# processor_board.net
KiCad netlist of a schematic drawn in EAGLE
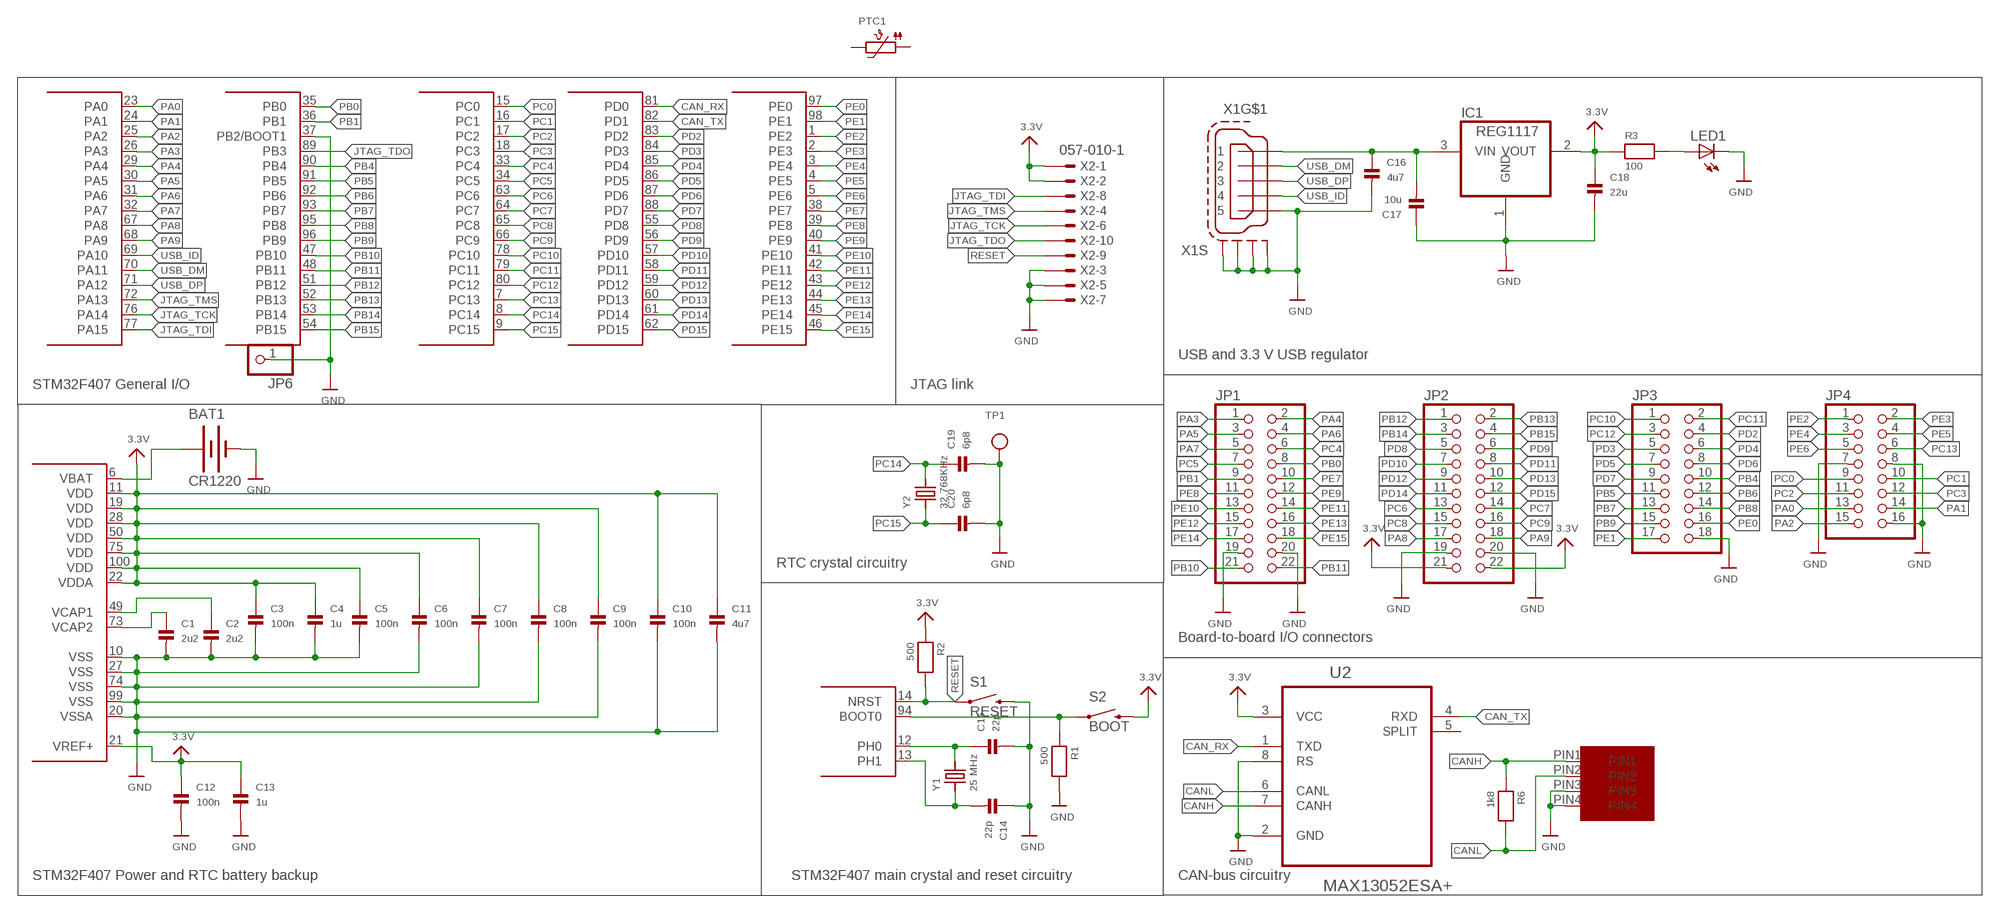
[diagram p0: schematic, sheet 1]

(export (version "E")
  (design (tool "Eeschema 10.0.6"))
  (components
    (comp (ref "BAT1")
      (value "CR1220")
      (footprint "eagle-import:BATTCON_12MM_PTH")
      (libsource (lib "eagle-import") (part "BATTERY12PTH"))
    )
    (comp (ref "C1")
      (value "2u2")
      (footprint "eagle-import:_0603MP")
      (libsource (lib "eagle-import") (part "CAP_CERAMIC_0603MP"))
    )
    (comp (ref "C2")
      (value "2u2")
      (footprint "eagle-import:_0603MP")
      (libsource (lib "eagle-import") (part "CAP_CERAMIC_0603MP"))
    )
    (comp (ref "C3")
      (value "100n")
      (footprint "eagle-import:_0603MP")
      (libsource (lib "eagle-import") (part "CAP_CERAMIC_0603MP"))
    )
    (comp (ref "C4")
      (value "1u")
      (footprint "eagle-import:_0603MP")
      (libsource (lib "eagle-import") (part "CAP_CERAMIC_0603MP"))
    )
    (comp (ref "C5")
      (value "100n")
      (footprint "eagle-import:_0603MP")
      (libsource (lib "eagle-import") (part "CAP_CERAMIC_0603MP"))
    )
    (comp (ref "C6")
      (value "100n")
      (footprint "eagle-import:_0603MP")
      (libsource (lib "eagle-import") (part "CAP_CERAMIC_0603MP"))
    )
    (comp (ref "C7")
      (value "100n")
      (footprint "eagle-import:_0603MP")
      (libsource (lib "eagle-import") (part "CAP_CERAMIC_0603MP"))
    )
    (comp (ref "C8")
      (value "100n")
      (footprint "eagle-import:_0603MP")
      (libsource (lib "eagle-import") (part "CAP_CERAMIC_0603MP"))
    )
    (comp (ref "C9")
      (value "100n")
      (footprint "eagle-import:_0603MP")
      (libsource (lib "eagle-import") (part "CAP_CERAMIC_0603MP"))
    )
    (comp (ref "C10")
      (value "100n")
      (footprint "eagle-import:_0603MP")
      (libsource (lib "eagle-import") (part "CAP_CERAMIC_0603MP"))
    )
    (comp (ref "C11")
      (value "4u7")
      (footprint "eagle-import:_0603MP")
      (libsource (lib "eagle-import") (part "CAP_CERAMIC_0603MP"))
    )
    (comp (ref "C12")
      (value "100n")
      (footprint "eagle-import:_0603MP")
      (libsource (lib "eagle-import") (part "CAP_CERAMIC_0603MP"))
    )
    (comp (ref "C13")
      (value "1u")
      (footprint "eagle-import:_0603MP")
      (libsource (lib "eagle-import") (part "CAP_CERAMIC_0603MP"))
    )
    (comp (ref "C14")
      (value "22p")
      (footprint "eagle-import:_0603MP")
      (libsource (lib "eagle-import") (part "CAP_CERAMIC_0603MP"))
    )
    (comp (ref "C15")
      (value "22p")
      (footprint "eagle-import:_0603MP")
      (libsource (lib "eagle-import") (part "CAP_CERAMIC_0603MP"))
    )
    (comp (ref "C16")
      (value "4u7")
      (footprint "eagle-import:_0603MP")
      (libsource (lib "eagle-import") (part "CAP_CERAMIC_0603MP"))
    )
    (comp (ref "C17")
      (value "10u")
      (footprint "eagle-import:_0603MP")
      (libsource (lib "eagle-import") (part "CAP_CERAMIC_0603MP"))
    )
    (comp (ref "C18")
      (value "22u")
      (footprint "eagle-import:_0603MP")
      (libsource (lib "eagle-import") (part "CAP_CERAMIC_0603MP"))
    )
    (comp (ref "C19")
      (value "6p8")
      (footprint "eagle-import:_0603MP")
      (libsource (lib "eagle-import") (part "CAP_CERAMIC_0603MP"))
    )
    (comp (ref "C20")
      (value "6p8")
      (footprint "eagle-import:_0603MP")
      (libsource (lib "eagle-import") (part "CAP_CERAMIC_0603MP"))
    )
    (comp (ref "IC1")
      (value "REG1117")
      (footprint "eagle-import:SOT223")
      (libsource (lib "eagle-import") (part "REG1117"))
    )
    (comp (ref "JP1")
      (value "PINHD-2X11")
      (footprint "eagle-import:2X11")
      (libsource (lib "eagle-import") (part "PINHD-2X11"))
    )
    (comp (ref "JP2")
      (value "PINHD-2X11")
      (footprint "eagle-import:2X11")
      (libsource (lib "eagle-import") (part "PINHD-2X11"))
    )
    (comp (ref "JP3")
      (value "PINHD-2X9")
      (footprint "eagle-import:2X09")
      (libsource (lib "eagle-import") (part "PINHD-2X9"))
    )
    (comp (ref "JP4")
      (value "PINHD-2X8")
      (footprint "eagle-import:2X08")
      (libsource (lib "eagle-import") (part "PINHD-2X8"))
    )
    (comp (ref "JP6")
      (value "PINHD-1X1")
      (footprint "eagle-import:1X01")
      (libsource (lib "eagle-import") (part "PINHD-1X1"))
    )
    (comp (ref "LED1")
      (value "LEDCHIPLED_1206")
      (footprint "eagle-import:CHIPLED_1206")
      (libsource (lib "eagle-import") (part "LEDCHIPLED_1206"))
    )
    (comp (ref "PTC1")
      (value "PTC1206")
      (footprint "eagle-import:1206")
      (libsource (lib "eagle-import") (part "PTC1206"))
    )
    (comp (ref "R1")
      (value "500")
      (footprint "eagle-import:_0603MP")
      (libsource (lib "eagle-import") (part "RESISTOR_0603MP"))
    )
    (comp (ref "R2")
      (value "500")
      (footprint "eagle-import:_0603MP")
      (libsource (lib "eagle-import") (part "RESISTOR_0603MP"))
    )
    (comp (ref "R3")
      (value "100")
      (footprint "eagle-import:_0603MP")
      (libsource (lib "eagle-import") (part "RESISTOR_0603MP"))
    )
    (comp (ref "R6")
      (value "1k8")
      (footprint "eagle-import:_0603MP")
      (libsource (lib "eagle-import") (part "RESISTOR_0603MP"))
    )
    (comp (ref "S1")
      (value "RESET")
      (footprint "eagle-import:TACTILE-SWITCH-1101NE")
      (libsource (lib "eagle-import") (part "SWITCH-MOMENTARY-2SMD-1101NE"))
    )
    (comp (ref "S2")
      (value "BOOT")
      (footprint "eagle-import:TACTILE-SWITCH-1101NE")
      (libsource (lib "eagle-import") (part "SWITCH-MOMENTARY-2SMD-1101NE"))
    )
    (comp (ref "TP1")
      (value "TESTPOINT0.1\"")
      (footprint "eagle-import:1X01_ROUND")
      (libsource (lib "eagle-import") (part "TESTPOINT0.1{dblquote}"))
    )
    (comp (ref "U$23")
      (value "MICROFIT4")
      (footprint "eagle-import:MICROFIT4SOCK")
      (libsource (lib "eagle-import") (part "MICROFIT4"))
    )
    (comp (ref "U1")
      (value "STM32F4-100")
      (footprint "eagle-import:SQFP-S-14X14-100")
      (libsource (lib "eagle-import") (part "STM32F4-100"))
    )
    (comp (ref "U2")
      (value "MAX13052ESA+")
      (footprint "eagle-import:SOIC127P600X175-8N")
      (libsource (lib "eagle-import") (part "MAX13052ESA+"))
    )
    (comp (ref "X1")
      (value "MINI-USB-SCHIELD-32005-201")
      (footprint "eagle-import:32005-201")
      (libsource (lib "eagle-import") (part "MINI-USB-SCHIELD-32005-201"))
    )
    (comp (ref "X2")
      (value "057-010-1")
      (footprint "eagle-import:057-010-1")
      (libsource (lib "eagle-import") (part "057-010-1"))
    )
    (comp (ref "Y1")
      (value "25 MHz")
      (footprint "eagle-import:CRYSTAL_2.5X2")
      (libsource (lib "eagle-import") (part "CRYSTAL2.5X2.0MM"))
    )
    (comp (ref "Y2")
      (value "32.768KHz")
      (footprint "eagle-import:CRYSTAL_CYL_2X6MM_SMT")
      (libsource (lib "eagle-import") (part "CRYSTAL32.768"))
    )
  )
  (nets
    (net (code "1") (name "3.3V") (class "Default")
      (node (ref "C10") (pin "1") (pinfunction "P$1_1") (pintype "passive"))
      (node (ref "C11") (pin "1") (pinfunction "P$1_1") (pintype "passive"))
      (node (ref "C12") (pin "1") (pinfunction "P$1_1") (pintype "passive"))
      (node (ref "C13") (pin "1") (pinfunction "P$1_1") (pintype "passive"))
      (node (ref "C18") (pin "1") (pinfunction "P$1_1") (pintype "passive"))
      (node (ref "C3") (pin "1") (pinfunction "P$1_1") (pintype "passive"))
      (node (ref "C4") (pin "1") (pinfunction "P$1_1") (pintype "passive"))
      (node (ref "C5") (pin "1") (pinfunction "P$1_1") (pintype "passive"))
      (node (ref "C6") (pin "1") (pinfunction "P$1_1") (pintype "passive"))
      (node (ref "C7") (pin "1") (pinfunction "P$1_1") (pintype "passive"))
      (node (ref "C8") (pin "1") (pinfunction "P$1_1") (pintype "passive"))
      (node (ref "C9") (pin "1") (pinfunction "P$1_1") (pintype "passive"))
      (node (ref "IC1") (pin "2") (pinfunction "VOUT_2") (pintype "output"))
      (node (ref "JP2") (pin "21") (pinfunction "21_21") (pintype "passive"))
      (node (ref "JP2") (pin "22") (pinfunction "22_22") (pintype "passive"))
      (node (ref "R2") (pin "1") (pinfunction "1_1") (pintype "passive"))
      (node (ref "R3") (pin "1") (pinfunction "1_1") (pintype "passive"))
      (node (ref "S2") (pin "2") (pinfunction "2_2") (pintype "passive"))
      (node (ref "U1") (pin "100") (pinfunction "VDD_100") (pintype "power_in"))
      (node (ref "U1") (pin "11") (pinfunction "VDD_11") (pintype "power_in"))
      (node (ref "U1") (pin "19") (pinfunction "VDD_19") (pintype "power_in"))
      (node (ref "U1") (pin "21") (pinfunction "VREF+_21") (pintype "passive"))
      (node (ref "U1") (pin "22") (pinfunction "VDDA_22") (pintype "power_in"))
      (node (ref "U1") (pin "28") (pinfunction "VDD_28") (pintype "power_in"))
      (node (ref "U1") (pin "50") (pinfunction "VDD_50") (pintype "power_in"))
      (node (ref "U1") (pin "75") (pinfunction "VDD_75") (pintype "power_in"))
      (node (ref "U2") (pin "3") (pinfunction "VCC_3") (pintype "power_in"))
      (node (ref "X2") (pin "1") (pinfunction "S_1") (pintype "passive"))
      (node (ref "X2") (pin "2") (pinfunction "S_2") (pintype "passive"))
    )
    (net (code "2") (name "CANH") (class "Default")
      (node (ref "R6") (pin "1") (pinfunction "1_1") (pintype "passive"))
      (node (ref "U$23") (pin "PIN1") (pinfunction "PIN1_PIN1") (pintype "bidirectional"))
      (node (ref "U2") (pin "7") (pinfunction "CANH_7") (pintype "input"))
    )
    (net (code "3") (name "CANL") (class "Default")
      (node (ref "R6") (pin "2") (pinfunction "2_2") (pintype "passive"))
      (node (ref "U$23") (pin "PIN2") (pinfunction "PIN2_PIN2") (pintype "bidirectional"))
      (node (ref "U2") (pin "6") (pinfunction "CANL_6") (pintype "input"))
    )
    (net (code "4") (name "CAN_RX") (class "Default")
      (node (ref "U1") (pin "81") (pinfunction "PD0_81") (pintype "bidirectional"))
      (node (ref "U2") (pin "1") (pinfunction "TXD_1") (pintype "input"))
    )
    (net (code "5") (name "CAN_TX") (class "Default")
      (node (ref "U1") (pin "82") (pinfunction "PD1_82") (pintype "bidirectional"))
      (node (ref "U2") (pin "4") (pinfunction "RXD_4") (pintype "output"))
    )
    (net (code "6") (name "GND") (class "Default")
      (node (ref "BAT1") (pin "GND") (pinfunction "-_GND") (pintype "power_in"))
      (node (ref "C1") (pin "2") (pinfunction "P$2_2") (pintype "passive"))
      (node (ref "C10") (pin "2") (pinfunction "P$2_2") (pintype "passive"))
      (node (ref "C11") (pin "2") (pinfunction "P$2_2") (pintype "passive"))
      (node (ref "C12") (pin "2") (pinfunction "P$2_2") (pintype "passive"))
      (node (ref "C13") (pin "2") (pinfunction "P$2_2") (pintype "passive"))
      (node (ref "C14") (pin "1") (pinfunction "P$1_1") (pintype "passive"))
      (node (ref "C15") (pin "2") (pinfunction "P$2_2") (pintype "passive"))
      (node (ref "C16") (pin "2") (pinfunction "P$2_2") (pintype "passive"))
      (node (ref "C17") (pin "1") (pinfunction "P$1_1") (pintype "passive"))
      (node (ref "C18") (pin "2") (pinfunction "P$2_2") (pintype "passive"))
      (node (ref "C19") (pin "2") (pinfunction "P$2_2") (pintype "passive"))
      (node (ref "C2") (pin "2") (pinfunction "P$2_2") (pintype "passive"))
      (node (ref "C20") (pin "2") (pinfunction "P$2_2") (pintype "passive"))
      (node (ref "C3") (pin "2") (pinfunction "P$2_2") (pintype "passive"))
      (node (ref "C4") (pin "2") (pinfunction "P$2_2") (pintype "passive"))
      (node (ref "C5") (pin "2") (pinfunction "P$2_2") (pintype "passive"))
      (node (ref "C6") (pin "2") (pinfunction "P$2_2") (pintype "passive"))
      (node (ref "C7") (pin "2") (pinfunction "P$2_2") (pintype "passive"))
      (node (ref "C8") (pin "2") (pinfunction "P$2_2") (pintype "passive"))
      (node (ref "C9") (pin "2") (pinfunction "P$2_2") (pintype "passive"))
      (node (ref "IC1") (pin "1") (pinfunction "GND_1") (pintype "power_in"))
      (node (ref "JP1") (pin "19") (pinfunction "19_19") (pintype "passive"))
      (node (ref "JP1") (pin "20") (pinfunction "20_20") (pintype "passive"))
      (node (ref "JP2") (pin "19") (pinfunction "19_19") (pintype "passive"))
      (node (ref "JP2") (pin "20") (pinfunction "20_20") (pintype "passive"))
      (node (ref "JP3") (pin "18") (pinfunction "18_18") (pintype "passive"))
      (node (ref "JP4") (pin "16") (pinfunction "16_16") (pintype "passive"))
      (node (ref "JP4") (pin "7") (pinfunction "7_7") (pintype "passive"))
      (node (ref "JP4") (pin "8") (pinfunction "8_8") (pintype "passive"))
      (node (ref "JP6") (pin "1") (pinfunction "1_1") (pintype "passive"))
      (node (ref "LED1") (pin "C") (pinfunction "C_C") (pintype "passive"))
      (node (ref "R1") (pin "2") (pinfunction "2_2") (pintype "passive"))
      (node (ref "S1") (pin "2") (pinfunction "2_2") (pintype "passive"))
      (node (ref "TP1") (pin "1") (pinfunction "P$1_1") (pintype "bidirectional"))
      (node (ref "U$23") (pin "PIN3") (pinfunction "PIN3_PIN3") (pintype "bidirectional"))
      (node (ref "U$23") (pin "PIN4") (pinfunction "PIN4_PIN4") (pintype "bidirectional"))
      (node (ref "U1") (pin "10") (pinfunction "VSS_10") (pintype "power_in"))
      (node (ref "U1") (pin "20") (pinfunction "VSSA_20") (pintype "power_in"))
      (node (ref "U1") (pin "27") (pinfunction "VSS_27") (pintype "power_in"))
      (node (ref "U1") (pin "37") (pinfunction "PB2/BOOT1_37") (pintype "bidirectional"))
      (node (ref "U1") (pin "74") (pinfunction "VSS_74") (pintype "power_in"))
      (node (ref "U1") (pin "99") (pinfunction "VSS_99") (pintype "power_in"))
      (node (ref "U2") (pin "2") (pinfunction "GND_2") (pintype "passive"))
      (node (ref "U2") (pin "8") (pinfunction "RS_8") (pintype "input"))
      (node (ref "X1") (pin "5") (pinfunction "5_5") (pintype "passive"))
      (node (ref "X1") (pin "M1") (pinfunction "S1_M1") (pintype "passive"))
      (node (ref "X1") (pin "M2") (pinfunction "S2_M2") (pintype "passive"))
      (node (ref "X1") (pin "M3") (pinfunction "S3_M3") (pintype "passive"))
      (node (ref "X1") (pin "M4") (pinfunction "S4_M4") (pintype "passive"))
      (node (ref "X2") (pin "3") (pinfunction "S_3") (pintype "passive"))
      (node (ref "X2") (pin "5") (pinfunction "S_5") (pintype "passive"))
      (node (ref "X2") (pin "7") (pinfunction "S_7") (pintype "passive"))
    )
    (net (code "7") (name "JTAG_TCK") (class "Default")
      (node (ref "U1") (pin "76") (pinfunction "PA14_76") (pintype "bidirectional"))
      (node (ref "X2") (pin "6") (pinfunction "S_6") (pintype "passive"))
    )
    (net (code "8") (name "JTAG_TDI") (class "Default")
      (node (ref "U1") (pin "77") (pinfunction "PA15_77") (pintype "bidirectional"))
      (node (ref "X2") (pin "8") (pinfunction "S_8") (pintype "passive"))
    )
    (net (code "9") (name "JTAG_TDO") (class "Default")
      (node (ref "U1") (pin "89") (pinfunction "PB3_89") (pintype "bidirectional"))
      (node (ref "X2") (pin "10") (pinfunction "S_10") (pintype "passive"))
    )
    (net (code "10") (name "JTAG_TMS") (class "Default")
      (node (ref "U1") (pin "72") (pinfunction "PA13_72") (pintype "bidirectional"))
      (node (ref "X2") (pin "4") (pinfunction "S_4") (pintype "passive"))
    )
    (net (code "11") (name "Net-(BAT1-+)") (class "Default")
      (node (ref "BAT1") (pin "VCC@1") (pinfunction "+_VCC@1") (pintype "power_in"))
      (node (ref "U1") (pin "6") (pinfunction "VBAT_6") (pintype "power_in"))
    )
    (net (code "12") (name "Net-(C1-P$1)") (class "Default")
      (node (ref "C1") (pin "1") (pinfunction "P$1_1") (pintype "passive"))
      (node (ref "U1") (pin "73") (pinfunction "VCAP2_73") (pintype "passive"))
    )
    (net (code "13") (name "Net-(C2-P$1)") (class "Default")
      (node (ref "C2") (pin "1") (pinfunction "P$1_1") (pintype "passive"))
      (node (ref "U1") (pin "49") (pinfunction "VCAP1_49") (pintype "passive"))
    )
    (net (code "14") (name "Net-(C14-P$2)") (class "Default")
      (node (ref "C14") (pin "2") (pinfunction "P$2_2") (pintype "passive"))
      (node (ref "U1") (pin "13") (pinfunction "PH1_13") (pintype "bidirectional"))
      (node (ref "Y1") (pin "1") (pinfunction "1_1") (pintype "passive"))
    )
    (net (code "15") (name "Net-(C15-P$1)") (class "Default")
      (node (ref "C15") (pin "1") (pinfunction "P$1_1") (pintype "passive"))
      (node (ref "U1") (pin "12") (pinfunction "PH0_12") (pintype "bidirectional"))
      (node (ref "Y1") (pin "3") (pinfunction "2_3") (pintype "passive"))
    )
    (net (code "16") (name "Net-(C16-P$1)") (class "Default")
      (node (ref "C16") (pin "1") (pinfunction "P$1_1") (pintype "passive"))
      (node (ref "C17") (pin "2") (pinfunction "P$2_2") (pintype "passive"))
      (node (ref "IC1") (pin "3") (pinfunction "VIN_3") (pintype "input"))
      (node (ref "X1") (pin "1") (pinfunction "1_1") (pintype "passive"))
    )
    (net (code "17") (name "Net-(LED1-PadA)") (class "Default")
      (node (ref "LED1") (pin "A") (pinfunction "A_A") (pintype "passive"))
      (node (ref "R3") (pin "2") (pinfunction "2_2") (pintype "passive"))
    )
    (net (code "18") (name "Net-(U1G-BOOT0)") (class "Default")
      (node (ref "R1") (pin "1") (pinfunction "1_1") (pintype "passive"))
      (node (ref "S2") (pin "1") (pinfunction "1_1") (pintype "passive"))
      (node (ref "U1") (pin "94") (pinfunction "BOOT0_94") (pintype "bidirectional"))
    )
    (net (code "19") (name "PA0") (class "Default")
      (node (ref "JP4") (pin "13") (pinfunction "13_13") (pintype "passive"))
      (node (ref "U1") (pin "23") (pinfunction "PA0_23") (pintype "bidirectional"))
    )
    (net (code "20") (name "PA1") (class "Default")
      (node (ref "JP4") (pin "14") (pinfunction "14_14") (pintype "passive"))
      (node (ref "U1") (pin "24") (pinfunction "PA1_24") (pintype "bidirectional"))
    )
    (net (code "21") (name "PA2") (class "Default")
      (node (ref "JP4") (pin "15") (pinfunction "15_15") (pintype "passive"))
      (node (ref "U1") (pin "25") (pinfunction "PA2_25") (pintype "bidirectional"))
    )
    (net (code "22") (name "PA3") (class "Default")
      (node (ref "JP1") (pin "1") (pinfunction "1_1") (pintype "passive"))
      (node (ref "U1") (pin "26") (pinfunction "PA3_26") (pintype "bidirectional"))
    )
    (net (code "23") (name "PA4") (class "Default")
      (node (ref "JP1") (pin "2") (pinfunction "2_2") (pintype "passive"))
      (node (ref "U1") (pin "29") (pinfunction "PA4_29") (pintype "bidirectional"))
    )
    (net (code "24") (name "PA5") (class "Default")
      (node (ref "JP1") (pin "3") (pinfunction "3_3") (pintype "passive"))
      (node (ref "U1") (pin "30") (pinfunction "PA5_30") (pintype "bidirectional"))
    )
    (net (code "25") (name "PA6") (class "Default")
      (node (ref "JP1") (pin "4") (pinfunction "4_4") (pintype "passive"))
      (node (ref "U1") (pin "31") (pinfunction "PA6_31") (pintype "bidirectional"))
    )
    (net (code "26") (name "PA7") (class "Default")
      (node (ref "JP1") (pin "5") (pinfunction "5_5") (pintype "passive"))
      (node (ref "U1") (pin "32") (pinfunction "PA7_32") (pintype "bidirectional"))
    )
    (net (code "27") (name "PA8") (class "Default")
      (node (ref "JP2") (pin "17") (pinfunction "17_17") (pintype "passive"))
      (node (ref "U1") (pin "67") (pinfunction "PA8_67") (pintype "bidirectional"))
    )
    (net (code "28") (name "PA9") (class "Default")
      (node (ref "JP2") (pin "18") (pinfunction "18_18") (pintype "passive"))
      (node (ref "U1") (pin "68") (pinfunction "PA9_68") (pintype "bidirectional"))
    )
    (net (code "29") (name "PB0") (class "Default")
      (node (ref "JP1") (pin "8") (pinfunction "8_8") (pintype "passive"))
      (node (ref "U1") (pin "35") (pinfunction "PB0_35") (pintype "bidirectional"))
    )
    (net (code "30") (name "PB1") (class "Default")
      (node (ref "JP1") (pin "9") (pinfunction "9_9") (pintype "passive"))
      (node (ref "U1") (pin "36") (pinfunction "PB1_36") (pintype "bidirectional"))
    )
    (net (code "31") (name "PB4") (class "Default")
      (node (ref "JP3") (pin "10") (pinfunction "10_10") (pintype "passive"))
      (node (ref "U1") (pin "90") (pinfunction "PB4_90") (pintype "bidirectional"))
    )
    (net (code "32") (name "PB5") (class "Default")
      (node (ref "JP3") (pin "11") (pinfunction "11_11") (pintype "passive"))
      (node (ref "U1") (pin "91") (pinfunction "PB5_91") (pintype "bidirectional"))
    )
    (net (code "33") (name "PB6") (class "Default")
      (node (ref "JP3") (pin "12") (pinfunction "12_12") (pintype "passive"))
      (node (ref "U1") (pin "92") (pinfunction "PB6_92") (pintype "bidirectional"))
    )
    (net (code "34") (name "PB7") (class "Default")
      (node (ref "JP3") (pin "13") (pinfunction "13_13") (pintype "passive"))
      (node (ref "U1") (pin "93") (pinfunction "PB7_93") (pintype "bidirectional"))
    )
    (net (code "35") (name "PB8") (class "Default")
      (node (ref "JP3") (pin "14") (pinfunction "14_14") (pintype "passive"))
      (node (ref "U1") (pin "95") (pinfunction "PB8_95") (pintype "bidirectional"))
    )
    (net (code "36") (name "PB9") (class "Default")
      (node (ref "JP3") (pin "15") (pinfunction "15_15") (pintype "passive"))
      (node (ref "U1") (pin "96") (pinfunction "PB9_96") (pintype "bidirectional"))
    )
    (net (code "37") (name "PB10") (class "Default")
      (node (ref "JP1") (pin "21") (pinfunction "21_21") (pintype "passive"))
      (node (ref "U1") (pin "47") (pinfunction "PB10_47") (pintype "bidirectional"))
    )
    (net (code "38") (name "PB11") (class "Default")
      (node (ref "JP1") (pin "22") (pinfunction "22_22") (pintype "passive"))
      (node (ref "U1") (pin "48") (pinfunction "PB11_48") (pintype "bidirectional"))
    )
    (net (code "39") (name "PB12") (class "Default")
      (node (ref "JP2") (pin "1") (pinfunction "1_1") (pintype "passive"))
      (node (ref "U1") (pin "51") (pinfunction "PB12_51") (pintype "bidirectional"))
    )
    (net (code "40") (name "PB13") (class "Default")
      (node (ref "JP2") (pin "2") (pinfunction "2_2") (pintype "passive"))
      (node (ref "U1") (pin "52") (pinfunction "PB13_52") (pintype "bidirectional"))
    )
    (net (code "41") (name "PB14") (class "Default")
      (node (ref "JP2") (pin "3") (pinfunction "3_3") (pintype "passive"))
      (node (ref "U1") (pin "53") (pinfunction "PB14_53") (pintype "bidirectional"))
    )
    (net (code "42") (name "PB15") (class "Default")
      (node (ref "JP2") (pin "4") (pinfunction "4_4") (pintype "passive"))
      (node (ref "U1") (pin "54") (pinfunction "PB15_54") (pintype "bidirectional"))
    )
    (net (code "43") (name "PC0") (class "Default")
      (node (ref "JP4") (pin "9") (pinfunction "9_9") (pintype "passive"))
      (node (ref "U1") (pin "15") (pinfunction "PC0_15") (pintype "bidirectional"))
    )
    (net (code "44") (name "PC1") (class "Default")
      (node (ref "JP4") (pin "10") (pinfunction "10_10") (pintype "passive"))
      (node (ref "U1") (pin "16") (pinfunction "PC1_16") (pintype "bidirectional"))
    )
    (net (code "45") (name "PC2") (class "Default")
      (node (ref "JP4") (pin "11") (pinfunction "11_11") (pintype "passive"))
      (node (ref "U1") (pin "17") (pinfunction "PC2_17") (pintype "bidirectional"))
    )
    (net (code "46") (name "PC3") (class "Default")
      (node (ref "JP4") (pin "12") (pinfunction "12_12") (pintype "passive"))
      (node (ref "U1") (pin "18") (pinfunction "PC3_18") (pintype "bidirectional"))
    )
    (net (code "47") (name "PC4") (class "Default")
      (node (ref "JP1") (pin "6") (pinfunction "6_6") (pintype "passive"))
      (node (ref "U1") (pin "33") (pinfunction "PC4_33") (pintype "bidirectional"))
    )
    (net (code "48") (name "PC5") (class "Default")
      (node (ref "JP1") (pin "7") (pinfunction "7_7") (pintype "passive"))
      (node (ref "U1") (pin "34") (pinfunction "PC5_34") (pintype "bidirectional"))
    )
    (net (code "49") (name "PC6") (class "Default")
      (node (ref "JP2") (pin "13") (pinfunction "13_13") (pintype "passive"))
      (node (ref "U1") (pin "63") (pinfunction "PC6_63") (pintype "bidirectional"))
    )
    (net (code "50") (name "PC7") (class "Default")
      (node (ref "JP2") (pin "14") (pinfunction "14_14") (pintype "passive"))
      (node (ref "U1") (pin "64") (pinfunction "PC7_64") (pintype "bidirectional"))
    )
    (net (code "51") (name "PC8") (class "Default")
      (node (ref "JP2") (pin "15") (pinfunction "15_15") (pintype "passive"))
      (node (ref "U1") (pin "65") (pinfunction "PC8_65") (pintype "bidirectional"))
    )
    (net (code "52") (name "PC9") (class "Default")
      (node (ref "JP2") (pin "16") (pinfunction "16_16") (pintype "passive"))
      (node (ref "U1") (pin "66") (pinfunction "PC9_66") (pintype "bidirectional"))
    )
    (net (code "53") (name "PC10") (class "Default")
      (node (ref "JP3") (pin "1") (pinfunction "1_1") (pintype "passive"))
      (node (ref "U1") (pin "78") (pinfunction "PC10_78") (pintype "bidirectional"))
    )
    (net (code "54") (name "PC11") (class "Default")
      (node (ref "JP3") (pin "2") (pinfunction "2_2") (pintype "passive"))
      (node (ref "U1") (pin "79") (pinfunction "PC11_79") (pintype "bidirectional"))
    )
    (net (code "55") (name "PC12") (class "Default")
      (node (ref "JP3") (pin "3") (pinfunction "3_3") (pintype "passive"))
      (node (ref "U1") (pin "80") (pinfunction "PC12_80") (pintype "bidirectional"))
    )
    (net (code "56") (name "PC13") (class "Default")
      (node (ref "JP4") (pin "6") (pinfunction "6_6") (pintype "passive"))
      (node (ref "U1") (pin "7") (pinfunction "PC13_7") (pintype "bidirectional"))
    )
    (net (code "57") (name "PC14") (class "Default")
      (node (ref "C19") (pin "1") (pinfunction "P$1_1") (pintype "passive"))
      (node (ref "U1") (pin "8") (pinfunction "PC14_8") (pintype "bidirectional"))
      (node (ref "Y2") (pin "2") (pinfunction "2_2") (pintype "passive"))
    )
    (net (code "58") (name "PC15") (class "Default")
      (node (ref "C20") (pin "1") (pinfunction "P$1_1") (pintype "passive"))
      (node (ref "U1") (pin "9") (pinfunction "PC15_9") (pintype "bidirectional"))
      (node (ref "Y2") (pin "1") (pinfunction "1_1") (pintype "passive"))
    )
    (net (code "59") (name "PD2") (class "Default")
      (node (ref "JP3") (pin "4") (pinfunction "4_4") (pintype "passive"))
      (node (ref "U1") (pin "83") (pinfunction "PD2_83") (pintype "bidirectional"))
    )
    (net (code "60") (name "PD3") (class "Default")
      (node (ref "JP3") (pin "5") (pinfunction "5_5") (pintype "passive"))
      (node (ref "U1") (pin "84") (pinfunction "PD3_84") (pintype "bidirectional"))
    )
    (net (code "61") (name "PD4") (class "Default")
      (node (ref "JP3") (pin "6") (pinfunction "6_6") (pintype "passive"))
      (node (ref "U1") (pin "85") (pinfunction "PD4_85") (pintype "bidirectional"))
    )
    (net (code "62") (name "PD5") (class "Default")
      (node (ref "JP3") (pin "7") (pinfunction "7_7") (pintype "passive"))
      (node (ref "U1") (pin "86") (pinfunction "PD5_86") (pintype "bidirectional"))
    )
    (net (code "63") (name "PD6") (class "Default")
      (node (ref "JP3") (pin "8") (pinfunction "8_8") (pintype "passive"))
      (node (ref "U1") (pin "87") (pinfunction "PD6_87") (pintype "bidirectional"))
    )
    (net (code "64") (name "PD7") (class "Default")
      (node (ref "JP3") (pin "9") (pinfunction "9_9") (pintype "passive"))
      (node (ref "U1") (pin "88") (pinfunction "PD7_88") (pintype "bidirectional"))
    )
    (net (code "65") (name "PD8") (class "Default")
      (node (ref "JP2") (pin "5") (pinfunction "5_5") (pintype "passive"))
      (node (ref "U1") (pin "55") (pinfunction "PD8_55") (pintype "bidirectional"))
    )
    (net (code "66") (name "PD9") (class "Default")
      (node (ref "JP2") (pin "6") (pinfunction "6_6") (pintype "passive"))
      (node (ref "U1") (pin "56") (pinfunction "PD9_56") (pintype "bidirectional"))
    )
    (net (code "67") (name "PD10") (class "Default")
      (node (ref "JP2") (pin "7") (pinfunction "7_7") (pintype "passive"))
      (node (ref "U1") (pin "57") (pinfunction "PD10_57") (pintype "bidirectional"))
    )
    (net (code "68") (name "PD11") (class "Default")
      (node (ref "JP2") (pin "8") (pinfunction "8_8") (pintype "passive"))
      (node (ref "U1") (pin "58") (pinfunction "PD11_58") (pintype "bidirectional"))
    )
    (net (code "69") (name "PD12") (class "Default")
      (node (ref "JP2") (pin "9") (pinfunction "9_9") (pintype "passive"))
      (node (ref "U1") (pin "59") (pinfunction "PD12_59") (pintype "bidirectional"))
    )
    (net (code "70") (name "PD13") (class "Default")
      (node (ref "JP2") (pin "10") (pinfunction "10_10") (pintype "passive"))
      (node (ref "U1") (pin "60") (pinfunction "PD13_60") (pintype "bidirectional"))
    )
    (net (code "71") (name "PD14") (class "Default")
      (node (ref "JP2") (pin "11") (pinfunction "11_11") (pintype "passive"))
      (node (ref "U1") (pin "61") (pinfunction "PD14_61") (pintype "bidirectional"))
    )
    (net (code "72") (name "PD15") (class "Default")
      (node (ref "JP2") (pin "12") (pinfunction "12_12") (pintype "passive"))
      (node (ref "U1") (pin "62") (pinfunction "PD15_62") (pintype "bidirectional"))
    )
    (net (code "73") (name "PE0") (class "Default")
      (node (ref "JP3") (pin "16") (pinfunction "16_16") (pintype "passive"))
      (node (ref "U1") (pin "97") (pinfunction "PE0_97") (pintype "bidirectional"))
    )
    (net (code "74") (name "PE1") (class "Default")
      (node (ref "JP3") (pin "17") (pinfunction "17_17") (pintype "passive"))
      (node (ref "U1") (pin "98") (pinfunction "PE1_98") (pintype "bidirectional"))
    )
    (net (code "75") (name "PE2") (class "Default")
      (node (ref "JP4") (pin "1") (pinfunction "1_1") (pintype "passive"))
      (node (ref "U1") (pin "1") (pinfunction "PE2_1") (pintype "bidirectional"))
    )
    (net (code "76") (name "PE3") (class "Default")
      (node (ref "JP4") (pin "2") (pinfunction "2_2") (pintype "passive"))
      (node (ref "U1") (pin "2") (pinfunction "PE3_2") (pintype "bidirectional"))
    )
    (net (code "77") (name "PE4") (class "Default")
      (node (ref "JP4") (pin "3") (pinfunction "3_3") (pintype "passive"))
      (node (ref "U1") (pin "3") (pinfunction "PE4_3") (pintype "bidirectional"))
    )
    (net (code "78") (name "PE5") (class "Default")
      (node (ref "JP4") (pin "4") (pinfunction "4_4") (pintype "passive"))
      (node (ref "U1") (pin "4") (pinfunction "PE5_4") (pintype "bidirectional"))
    )
    (net (code "79") (name "PE6") (class "Default")
      (node (ref "JP4") (pin "5") (pinfunction "5_5") (pintype "passive"))
      (node (ref "U1") (pin "5") (pinfunction "PE6_5") (pintype "bidirectional"))
    )
    (net (code "80") (name "PE7") (class "Default")
      (node (ref "JP1") (pin "10") (pinfunction "10_10") (pintype "passive"))
      (node (ref "U1") (pin "38") (pinfunction "PE7_38") (pintype "bidirectional"))
    )
    (net (code "81") (name "PE8") (class "Default")
      (node (ref "JP1") (pin "11") (pinfunction "11_11") (pintype "passive"))
      (node (ref "U1") (pin "39") (pinfunction "PE8_39") (pintype "bidirectional"))
    )
    (net (code "82") (name "PE9") (class "Default")
      (node (ref "JP1") (pin "12") (pinfunction "12_12") (pintype "passive"))
      (node (ref "U1") (pin "40") (pinfunction "PE9_40") (pintype "bidirectional"))
    )
    (net (code "83") (name "PE10") (class "Default")
      (node (ref "JP1") (pin "13") (pinfunction "13_13") (pintype "passive"))
      (node (ref "U1") (pin "41") (pinfunction "PE10_41") (pintype "bidirectional"))
    )
    (net (code "84") (name "PE11") (class "Default")
      (node (ref "JP1") (pin "14") (pinfunction "14_14") (pintype "passive"))
      (node (ref "U1") (pin "42") (pinfunction "PE11_42") (pintype "bidirectional"))
    )
    (net (code "85") (name "PE12") (class "Default")
      (node (ref "JP1") (pin "15") (pinfunction "15_15") (pintype "passive"))
      (node (ref "U1") (pin "43") (pinfunction "PE12_43") (pintype "bidirectional"))
    )
    (net (code "86") (name "PE13") (class "Default")
      (node (ref "JP1") (pin "16") (pinfunction "16_16") (pintype "passive"))
      (node (ref "U1") (pin "44") (pinfunction "PE13_44") (pintype "bidirectional"))
    )
    (net (code "87") (name "PE14") (class "Default")
      (node (ref "JP1") (pin "17") (pinfunction "17_17") (pintype "passive"))
      (node (ref "U1") (pin "45") (pinfunction "PE14_45") (pintype "bidirectional"))
    )
    (net (code "88") (name "PE15") (class "Default")
      (node (ref "JP1") (pin "18") (pinfunction "18_18") (pintype "passive"))
      (node (ref "U1") (pin "46") (pinfunction "PE15_46") (pintype "bidirectional"))
    )
    (net (code "89") (name "RESET") (class "Default")
      (node (ref "R2") (pin "2") (pinfunction "2_2") (pintype "passive"))
      (node (ref "S1") (pin "1") (pinfunction "1_1") (pintype "passive"))
      (node (ref "U1") (pin "14") (pinfunction "NRST_14") (pintype "bidirectional"))
      (node (ref "X2") (pin "9") (pinfunction "S_9") (pintype "passive"))
    )
    (net (code "90") (name "USB_DM") (class "Default")
      (node (ref "U1") (pin "70") (pinfunction "PA11_70") (pintype "bidirectional"))
      (node (ref "X1") (pin "2") (pinfunction "2_2") (pintype "passive"))
    )
    (net (code "91") (name "USB_DP") (class "Default")
      (node (ref "U1") (pin "71") (pinfunction "PA12_71") (pintype "bidirectional"))
      (node (ref "X1") (pin "3") (pinfunction "3_3") (pintype "passive"))
    )
    (net (code "92") (name "USB_ID") (class "Default")
      (node (ref "U1") (pin "69") (pinfunction "PA10_69") (pintype "bidirectional"))
      (node (ref "X1") (pin "4") (pinfunction "4_4") (pintype "passive"))
    )
    (net (code "93") (name "unconnected-(PTC1-Pad1)") (class "Default")
      (node (ref "PTC1") (pin "1") (pinfunction "1_1") (pintype "passive"))
    )
    (net (code "94") (name "unconnected-(PTC1-Pad2)") (class "Default")
      (node (ref "PTC1") (pin "2") (pinfunction "2_2") (pintype "passive"))
    )
    (net (code "95") (name "unconnected-(U2-SPLIT-Pad5)") (class "Default")
      (node (ref "U2") (pin "5") (pinfunction "SPLIT_5") (pintype "output"))
    )
  )
)
